# ESP_SCH.net
KiCad netlist of a schematic drawn in EasyEDA
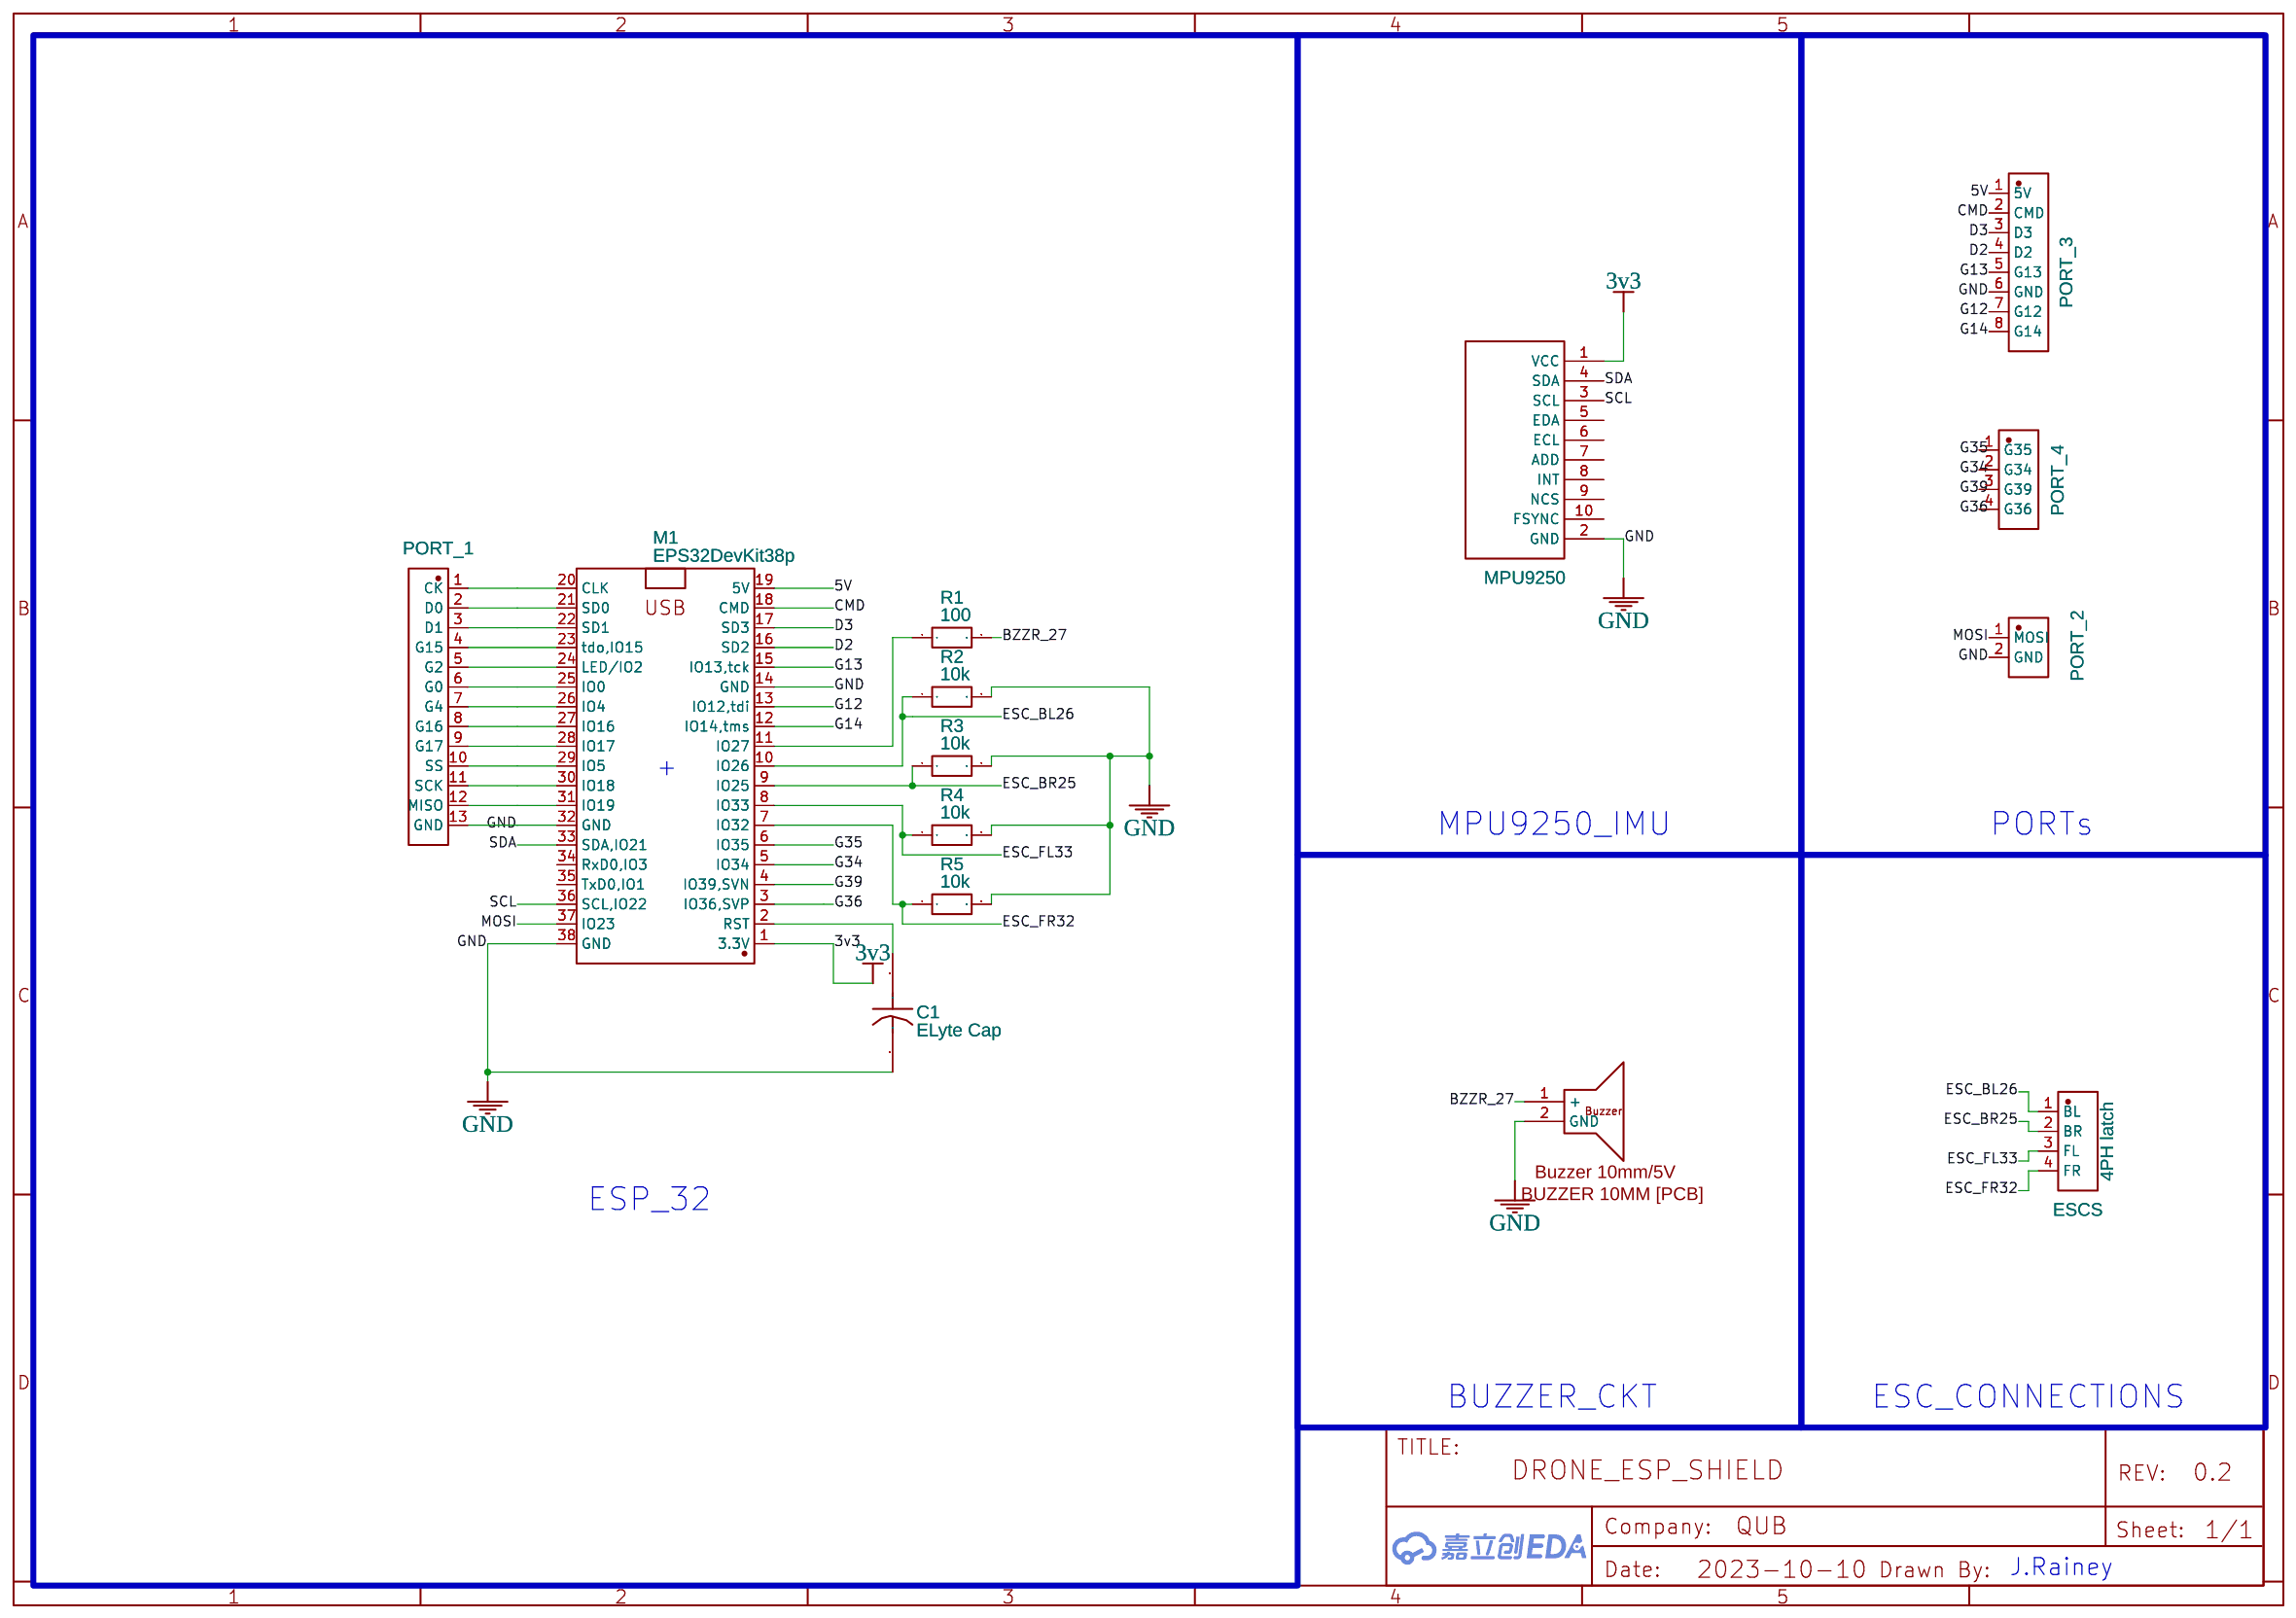
[diagram p0: schematic sheet]

(export (version "E")
  (design (tool "Eeschema 10.0.6"))
  (components
    (comp (ref "BUZZER")
      (value "Buzzer 10mm/5V")
      (fields (field (name "BOM_Manufacturer Part") "BUZZER"))
      (libsource (lib "") (part "Buzzer 10mm/5V"))
    )
    (comp (ref "C1") (value "ELyte Cap") (libsource (lib "") (part "Electrolitic Capacitor")))
    (comp (ref "ESCS")
      (value "4PH latch")
      (fields
        (field (name "BOM_Manufacturer Part") "A2541HWV-4P")
        (field (name "BOM_Supplier Part") "C5176037")
      )
      (libsource (lib "") (part "A2541HWV-4P_C5176037"))
    )
    (comp (ref "M1") (value "EPS32DevKit38p") (libsource (lib "") (part "EPS32DevKit38p")))
    (comp (ref "MPU9250") (value "MPU9250") (libsource (lib "") (part "MPU9250 MODULE")))
    (comp (ref "PORT_1")
      (value "EXT_PORT")
      (fields
        (field (name "BOM_Manufacturer Part") "PZ254-1-13-Z-8.5KK")
        (field (name "BOM_Supplier Part") "C3012215")
      )
      (libsource (lib "") (part "PZ254-1-13-Z-8.5KK"))
    )
    (comp (ref "PORT_2")
      (value "HDR102")
      (fields (field (name "BOM_Supplier Part") "C9900001420"))
      (libsource (lib "") (part "HDR102"))
    )
    (comp (ref "PORT_3")
      (value "Port_3")
      (fields (field (name "Manufacturer Part") "PZ254-1-08-Z-C") (field (name "Manufacturer") "HCTL(华灿天禄)"))
      (libsource (lib "") (part "PZ254-1-08-Z-C"))
    )
    (comp (ref "PORT_4")
      (value "0022285044")
      (fields (field (name "BOM_Supplier Part") "C9900016049"))
      (libsource (lib "") (part "0022285044"))
    )
    (comp (ref "R1") (value "100") (libsource (lib "") (part "R_AXIAL-0.4_EU")))
    (comp (ref "R2") (value "10k") (libsource (lib "") (part "R_AXIAL-0.4_EU")))
    (comp (ref "R3") (value "10k") (libsource (lib "") (part "R_AXIAL-0.4_EU")))
    (comp (ref "R4") (value "10k") (libsource (lib "") (part "R_AXIAL-0.4_EU")))
    (comp (ref "R5") (value "10k") (libsource (lib "") (part "R_AXIAL-0.4_EU")))
  )
  (nets
    (net (code "1") (name "/5V") (class "Default")
      (node (ref "M1") (pin "19") (pinfunction "5V_19") (pintype "unspecified"))
      (node (ref "PORT_3") (pin "1") (pinfunction "5V_1") (pintype "unspecified"))
    )
    (net (code "2") (name "/BZZR_27") (class "Default")
      (node (ref "BUZZER") (pin "1") (pinfunction "+_1") (pintype "unspecified"))
      (node (ref "R1") (pin "2") (pinfunction "2_2") (pintype "unspecified"))
    )
    (net (code "3") (name "/CMD") (class "Default")
      (node (ref "M1") (pin "18") (pinfunction "CMD_18") (pintype "unspecified"))
      (node (ref "PORT_3") (pin "2") (pinfunction "CMD_2") (pintype "unspecified"))
    )
    (net (code "4") (name "/D2") (class "Default")
      (node (ref "M1") (pin "16") (pinfunction "SD2_16") (pintype "unspecified"))
      (node (ref "PORT_3") (pin "4") (pinfunction "D2_4") (pintype "unspecified"))
    )
    (net (code "5") (name "/D3") (class "Default")
      (node (ref "M1") (pin "17") (pinfunction "SD3_17") (pintype "unspecified"))
      (node (ref "PORT_3") (pin "3") (pinfunction "D3_3") (pintype "unspecified"))
    )
    (net (code "6") (name "/ESC_BL26") (class "Default")
      (node (ref "ESCS") (pin "1") (pinfunction "BL_1") (pintype "unspecified"))
      (node (ref "M1") (pin "10") (pinfunction "IO26_10") (pintype "unspecified"))
      (node (ref "R2") (pin "1") (pinfunction "1_1") (pintype "unspecified"))
    )
    (net (code "7") (name "/ESC_BR25") (class "Default")
      (node (ref "ESCS") (pin "2") (pinfunction "BR_2") (pintype "unspecified"))
      (node (ref "M1") (pin "9") (pinfunction "IO25_9") (pintype "unspecified"))
      (node (ref "R3") (pin "1") (pinfunction "1_1") (pintype "unspecified"))
    )
    (net (code "8") (name "/ESC_FL33") (class "Default")
      (node (ref "ESCS") (pin "3") (pinfunction "FL_3") (pintype "unspecified"))
      (node (ref "M1") (pin "8") (pinfunction "IO33_8") (pintype "unspecified"))
      (node (ref "R4") (pin "1") (pinfunction "1_1") (pintype "unspecified"))
    )
    (net (code "9") (name "/ESC_FR32") (class "Default")
      (node (ref "ESCS") (pin "4") (pinfunction "FR_4") (pintype "unspecified"))
      (node (ref "M1") (pin "7") (pinfunction "IO32_7") (pintype "unspecified"))
      (node (ref "R5") (pin "1") (pinfunction "1_1") (pintype "unspecified"))
    )
    (net (code "10") (name "/G12") (class "Default")
      (node (ref "M1") (pin "13") (pinfunction "IO12,tdi_13") (pintype "unspecified"))
      (node (ref "PORT_3") (pin "7") (pinfunction "G12_7") (pintype "unspecified"))
    )
    (net (code "11") (name "/G13") (class "Default")
      (node (ref "M1") (pin "15") (pinfunction "IO13,tck_15") (pintype "unspecified"))
      (node (ref "PORT_3") (pin "5") (pinfunction "G13_5") (pintype "unspecified"))
    )
    (net (code "12") (name "/G14") (class "Default")
      (node (ref "M1") (pin "12") (pinfunction "IO14,tms_12") (pintype "unspecified"))
      (node (ref "PORT_3") (pin "8") (pinfunction "G14_8") (pintype "unspecified"))
    )
    (net (code "13") (name "/G34") (class "Default")
      (node (ref "M1") (pin "5") (pinfunction "IO34_5") (pintype "unspecified"))
      (node (ref "PORT_4") (pin "2") (pinfunction "G34_2") (pintype "unspecified"))
    )
    (net (code "14") (name "/G35") (class "Default")
      (node (ref "M1") (pin "6") (pinfunction "IO35_6") (pintype "unspecified"))
      (node (ref "PORT_4") (pin "1") (pinfunction "G35_1") (pintype "unspecified"))
    )
    (net (code "15") (name "/G36") (class "Default")
      (node (ref "M1") (pin "3") (pinfunction "IO36,SVP_3") (pintype "unspecified"))
      (node (ref "PORT_4") (pin "4") (pinfunction "G36_4") (pintype "unspecified"))
    )
    (net (code "16") (name "/G39") (class "Default")
      (node (ref "M1") (pin "4") (pinfunction "IO39,SVN_4") (pintype "unspecified"))
      (node (ref "PORT_4") (pin "3") (pinfunction "G39_3") (pintype "unspecified"))
    )
    (net (code "17") (name "/MOSI") (class "Default")
      (node (ref "M1") (pin "37") (pinfunction "IO23_37") (pintype "unspecified"))
      (node (ref "PORT_2") (pin "1") (pinfunction "MOSI_1") (pintype "unspecified"))
    )
    (net (code "18") (name "/SCL") (class "Default")
      (node (ref "M1") (pin "36") (pinfunction "SCL,IO22_36") (pintype "unspecified"))
      (node (ref "MPU9250") (pin "3") (pinfunction "SCL_3") (pintype "bidirectional"))
    )
    (net (code "19") (name "/SDA") (class "Default")
      (node (ref "M1") (pin "33") (pinfunction "SDA,IO21_33") (pintype "unspecified"))
      (node (ref "MPU9250") (pin "4") (pinfunction "SDA_4") (pintype "bidirectional"))
    )
    (net (code "20") (name "3v3") (class "Default")
      (node (ref "M1") (pin "1") (pinfunction "3.3V_1") (pintype "unspecified"))
      (node (ref "MPU9250") (pin "1") (pinfunction "VCC_1") (pintype "passive"))
    )
    (net (code "21") (name "GND") (class "Default")
      (node (ref "BUZZER") (pin "2") (pinfunction "GND_2") (pintype "unspecified"))
      (node (ref "C1") (pin "2") (pinfunction "2_2") (pintype "unspecified"))
      (node (ref "M1") (pin "14") (pinfunction "GND_14") (pintype "unspecified"))
      (node (ref "M1") (pin "32") (pinfunction "GND_32") (pintype "unspecified"))
      (node (ref "M1") (pin "38") (pinfunction "GND_38") (pintype "unspecified"))
      (node (ref "MPU9250") (pin "2") (pinfunction "GND_2") (pintype "passive"))
      (node (ref "PORT_1") (pin "13") (pinfunction "GND_13") (pintype "unspecified"))
      (node (ref "PORT_2") (pin "2") (pinfunction "GND_2") (pintype "unspecified"))
      (node (ref "PORT_3") (pin "6") (pinfunction "GND_6") (pintype "unspecified"))
      (node (ref "R2") (pin "2") (pinfunction "2_2") (pintype "unspecified"))
      (node (ref "R3") (pin "2") (pinfunction "2_2") (pintype "unspecified"))
      (node (ref "R4") (pin "2") (pinfunction "2_2") (pintype "unspecified"))
      (node (ref "R5") (pin "2") (pinfunction "2_2") (pintype "unspecified"))
    )
    (net (code "22") (name "Net-(M1-CLK)") (class "Default")
      (node (ref "M1") (pin "20") (pinfunction "CLK_20") (pintype "unspecified"))
      (node (ref "PORT_1") (pin "1") (pinfunction "CK_1") (pintype "unspecified"))
    )
    (net (code "23") (name "Net-(M1-IO0)") (class "Default")
      (node (ref "M1") (pin "25") (pinfunction "IO0_25") (pintype "unspecified"))
      (node (ref "PORT_1") (pin "6") (pinfunction "G0_6") (pintype "unspecified"))
    )
    (net (code "24") (name "Net-(M1-IO4)") (class "Default")
      (node (ref "M1") (pin "26") (pinfunction "IO4_26") (pintype "unspecified"))
      (node (ref "PORT_1") (pin "7") (pinfunction "G4_7") (pintype "unspecified"))
    )
    (net (code "25") (name "Net-(M1-IO5)") (class "Default")
      (node (ref "M1") (pin "29") (pinfunction "IO5_29") (pintype "unspecified"))
      (node (ref "PORT_1") (pin "10") (pinfunction "SS_10") (pintype "unspecified"))
    )
    (net (code "26") (name "Net-(M1-IO16)") (class "Default")
      (node (ref "M1") (pin "27") (pinfunction "IO16_27") (pintype "unspecified"))
      (node (ref "PORT_1") (pin "8") (pinfunction "G16_8") (pintype "unspecified"))
    )
    (net (code "27") (name "Net-(M1-IO17)") (class "Default")
      (node (ref "M1") (pin "28") (pinfunction "IO17_28") (pintype "unspecified"))
      (node (ref "PORT_1") (pin "9") (pinfunction "G17_9") (pintype "unspecified"))
    )
    (net (code "28") (name "Net-(M1-IO18)") (class "Default")
      (node (ref "M1") (pin "30") (pinfunction "IO18_30") (pintype "unspecified"))
      (node (ref "PORT_1") (pin "11") (pinfunction "SCK_11") (pintype "unspecified"))
    )
    (net (code "29") (name "Net-(M1-IO19)") (class "Default")
      (node (ref "M1") (pin "31") (pinfunction "IO19_31") (pintype "unspecified"))
      (node (ref "PORT_1") (pin "12") (pinfunction "MISO_12") (pintype "unspecified"))
    )
    (net (code "30") (name "Net-(M1-IO27)") (class "Default")
      (node (ref "M1") (pin "11") (pinfunction "IO27_11") (pintype "unspecified"))
      (node (ref "R1") (pin "1") (pinfunction "1_1") (pintype "unspecified"))
    )
    (net (code "31") (name "Net-(M1-LED{slash}IO2)") (class "Default")
      (node (ref "M1") (pin "24") (pinfunction "LED/IO2_24") (pintype "unspecified"))
      (node (ref "PORT_1") (pin "5") (pinfunction "G2_5") (pintype "unspecified"))
    )
    (net (code "32") (name "Net-(M1-RST)") (class "Default")
      (node (ref "C1") (pin "1") (pinfunction "1_1") (pintype "unspecified"))
      (node (ref "M1") (pin "2") (pinfunction "RST_2") (pintype "unspecified"))
    )
    (net (code "33") (name "Net-(M1-SD0)") (class "Default")
      (node (ref "M1") (pin "21") (pinfunction "SD0_21") (pintype "unspecified"))
      (node (ref "PORT_1") (pin "2") (pinfunction "D0_2") (pintype "unspecified"))
    )
    (net (code "34") (name "Net-(M1-SD1)") (class "Default")
      (node (ref "M1") (pin "22") (pinfunction "SD1_22") (pintype "unspecified"))
      (node (ref "PORT_1") (pin "3") (pinfunction "D1_3") (pintype "unspecified"))
    )
    (net (code "35") (name "Net-(M1-tdo,IO15)") (class "Default")
      (node (ref "M1") (pin "23") (pinfunction "tdo,IO15_23") (pintype "unspecified"))
      (node (ref "PORT_1") (pin "4") (pinfunction "G15_4") (pintype "unspecified"))
    )
    (net (code "36") (name "unconnected-(M1-RxD0,IO3-Pad34)") (class "Default")
      (node (ref "M1") (pin "34") (pinfunction "RxD0,IO3_34") (pintype "unspecified"))
    )
    (net (code "37") (name "unconnected-(M1-TxD0,IO1-Pad35)") (class "Default")
      (node (ref "M1") (pin "35") (pinfunction "TxD0,IO1_35") (pintype "unspecified"))
    )
    (net (code "38") (name "unconnected-(MPU9250-ADD-Pad7)") (class "Default")
      (node (ref "MPU9250") (pin "7") (pinfunction "ADD_7") (pintype "bidirectional"))
    )
    (net (code "39") (name "unconnected-(MPU9250-ECL-Pad6)") (class "Default")
      (node (ref "MPU9250") (pin "6") (pinfunction "ECL_6") (pintype "bidirectional"))
    )
    (net (code "40") (name "unconnected-(MPU9250-EDA-Pad5)") (class "Default")
      (node (ref "MPU9250") (pin "5") (pinfunction "EDA_5") (pintype "bidirectional"))
    )
    (net (code "41") (name "unconnected-(MPU9250-FSYNC-Pad10)") (class "Default")
      (node (ref "MPU9250") (pin "10") (pinfunction "FSYNC_10") (pintype "bidirectional"))
    )
    (net (code "42") (name "unconnected-(MPU9250-INT-Pad8)") (class "Default")
      (node (ref "MPU9250") (pin "8") (pinfunction "INT_8") (pintype "bidirectional"))
    )
    (net (code "43") (name "unconnected-(MPU9250-NCS-Pad9)") (class "Default")
      (node (ref "MPU9250") (pin "9") (pinfunction "NCS_9") (pintype "bidirectional"))
    )
  )
)
